# Sheet2.net
KiCad netlist of a schematic drawn in Altium Designer
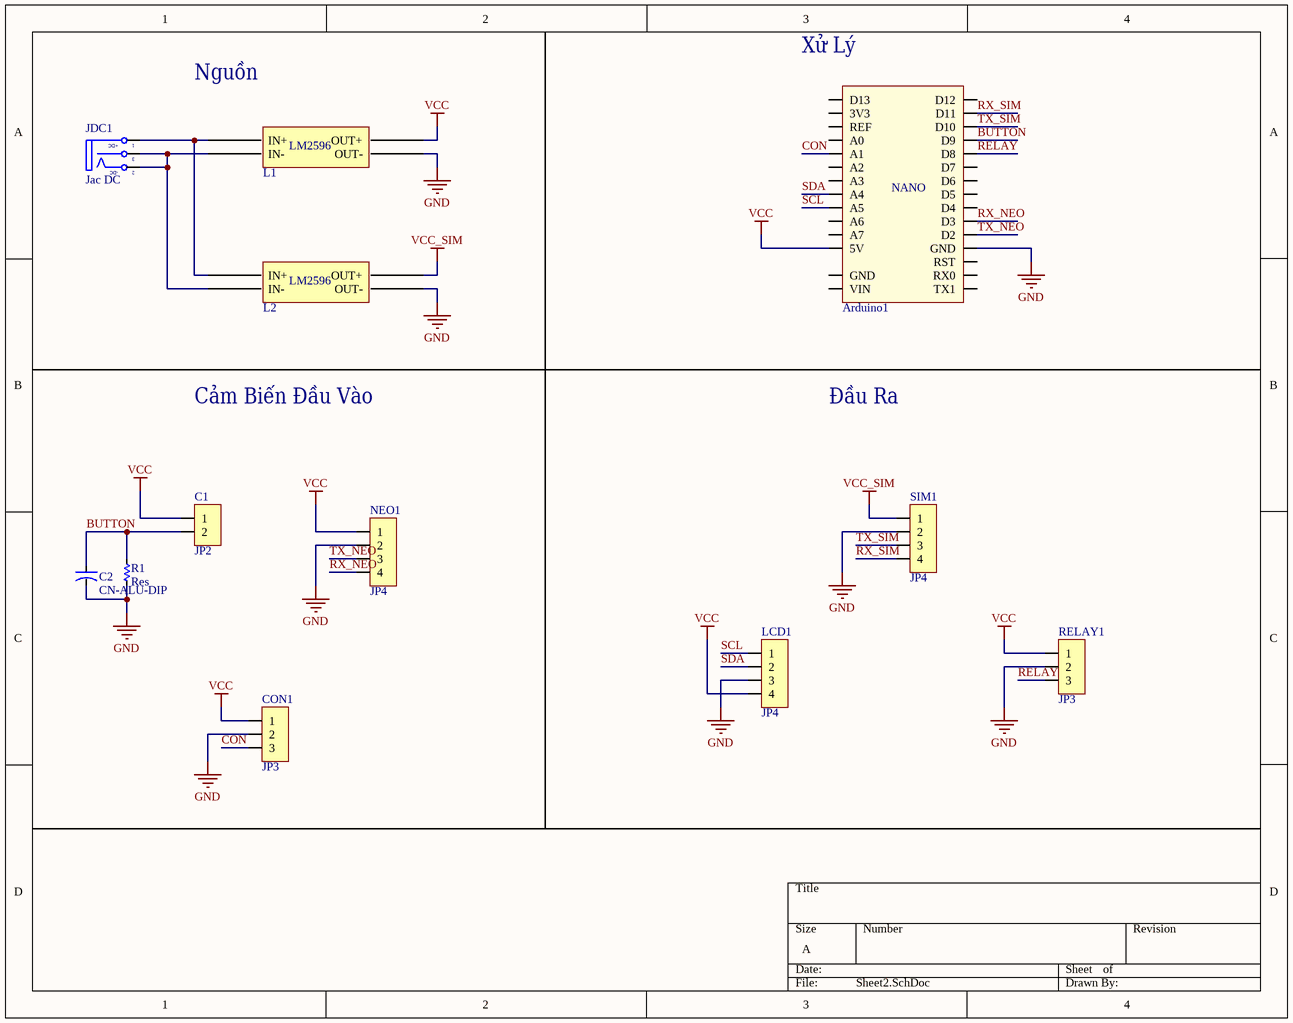
[diagram p0: Sheet2.SchDoc]

(export (version "E")
  (design (tool "Eeschema 10.0.6"))
  (components
    (comp (ref "Arduino1")
      (value "Arduino Nano")
      (footprint "Arduino Nano")
      (description "Arduino NANO")
      (libsource (lib "LIBRARY") (part "Arduino Nano"))
    )
    (comp (ref "C1")
      (value "JP2")
      (footprint "JP2-C1T")
      (description "WR-PHD 2.54 mm Angled Socket Header")
      (fields
        (field (name "MANUFACTURER") "Würth Elektronik eiSos GmbH")
        (field (name "PARTNO") "613002143121")
        (field (name "CREATED BY") "Karrer Zheng")
      )
      (libsource (lib "LIBRARY") (part "JP2"))
    )
    (comp (ref "C2")
      (value "CN-ALU-DIP")
      (footprint "CA-ALU-2.54")
      (description "Capacitor (Semiconductor SIM Model)")
      (fields (field (name "PUBLISHER") "Altium Limited"))
      (libsource (lib "LIBRARY") (part "CN-ALU-DIP"))
    )
    (comp (ref "CON1")
      (value "JP3")
      (footprint "JP3-C1T")
      (description "WR-PHD 2.54 mm Angled Socket Header")
      (fields
        (field (name "MANUFACTURER") "Würth Elektronik eiSos GmbH")
        (field (name "PARTNO") "613003143121")
        (field (name "CREATED BY") "Karrer Zheng")
      )
      (libsource (lib "LIBRARY") (part "JP3"))
    )
    (comp (ref "JDC1")
      (value "Jac DC")
      (footprint "DC0")
      (description "Jac DC input")
      (libsource (lib "LIBRARY") (part "DCIN"))
    )
    (comp (ref "L1")
      (value "BUCK_LM2596")
      (footprint "BUCK_LM2596")
      (libsource (lib "BUCK_LM2596_Sch") (part "BUCK_LM2596"))
    )
    (comp (ref "L2")
      (value "BUCK_LM2596")
      (footprint "BUCK_LM2596")
      (libsource (lib "BUCK_LM2596_Sch") (part "BUCK_LM2596"))
    )
    (comp (ref "LCD1")
      (value "JP4")
      (footprint "JP4-C1T")
      (description "WR-PHD 2.54 mm Angled Socket Header")
      (fields
        (field (name "MANUFACTURER") "Würth Elektronik eiSos GmbH")
        (field (name "PARTNO") "613004143121")
        (field (name "CREATED BY") "Karrer Zheng")
      )
      (libsource (lib "LIBRARY") (part "JP4"))
    )
    (comp (ref "NEO1")
      (value "JP4")
      (footprint "JP4-C1T")
      (description "WR-PHD 2.54 mm Angled Socket Header")
      (fields
        (field (name "MANUFACTURER") "Würth Elektronik eiSos GmbH")
        (field (name "PARTNO") "613004143121")
        (field (name "CREATED BY") "Karrer Zheng")
      )
      (libsource (lib "LIBRARY") (part "JP4"))
    )
    (comp (ref "R1")
      (value "Res")
      (footprint "RES-1/4W")
      (fields
        (field (name "MANUFACTURER") "Generic Components")
        (field (name "PUBLISHER") "Altium Hobart Technology Centre")
      )
      (libsource (lib "LIBRARY") (part "Res"))
    )
    (comp (ref "RELAY1")
      (value "JP3")
      (footprint "JP3-C1T")
      (description "WR-PHD 2.54 mm Angled Socket Header")
      (fields
        (field (name "MANUFACTURER") "Würth Elektronik eiSos GmbH")
        (field (name "PARTNO") "613003143121")
        (field (name "CREATED BY") "Karrer Zheng")
      )
      (libsource (lib "LIBRARY") (part "JP3"))
    )
    (comp (ref "SIM1")
      (value "JP4")
      (footprint "JP4-C1T")
      (description "WR-PHD 2.54 mm Angled Socket Header")
      (fields
        (field (name "MANUFACTURER") "Würth Elektronik eiSos GmbH")
        (field (name "PARTNO") "613004143121")
        (field (name "CREATED BY") "Karrer Zheng")
      )
      (libsource (lib "LIBRARY") (part "JP4"))
    )
  )
  (nets
    (net (code "1") (name "/BUTTON") (class "Default")
      (node (ref "Arduino1") (pin "D9") (pinfunction "D9_D9") (pintype "passive"))
      (node (ref "C1") (pin "2") (pinfunction "2_2") (pintype "passive"))
      (node (ref "C2") (pin "1") (pinfunction "1_1") (pintype "passive"))
      (node (ref "R1") (pin "1") (pinfunction "1_1") (pintype "passive"))
    )
    (net (code "2") (name "/CON") (class "Default")
      (node (ref "Arduino1") (pin "A1") (pinfunction "A1_A1") (pintype "passive"))
      (node (ref "CON1") (pin "3") (pinfunction "3_3") (pintype "passive"))
    )
    (net (code "3") (name "/RELAY") (class "Default")
      (node (ref "Arduino1") (pin "D8") (pinfunction "D8_D8") (pintype "passive"))
      (node (ref "RELAY1") (pin "3") (pinfunction "3_3") (pintype "passive"))
    )
    (net (code "4") (name "/RX_NEO") (class "Default")
      (node (ref "Arduino1") (pin "D3") (pinfunction "D3_D3") (pintype "passive"))
      (node (ref "NEO1") (pin "4") (pinfunction "4_4") (pintype "passive"))
    )
    (net (code "5") (name "/RX_SIM") (class "Default")
      (node (ref "Arduino1") (pin "D11") (pinfunction "D11_D11") (pintype "passive"))
      (node (ref "SIM1") (pin "4") (pinfunction "4_4") (pintype "passive"))
    )
    (net (code "6") (name "/SCL") (class "Default")
      (node (ref "Arduino1") (pin "A5") (pinfunction "A5_A5") (pintype "passive"))
      (node (ref "LCD1") (pin "1") (pinfunction "1_1") (pintype "passive"))
    )
    (net (code "7") (name "/SDA") (class "Default")
      (node (ref "Arduino1") (pin "A4") (pinfunction "A4_A4") (pintype "passive"))
      (node (ref "LCD1") (pin "2") (pinfunction "2_2") (pintype "passive"))
    )
    (net (code "8") (name "/TX_NEO") (class "Default")
      (node (ref "Arduino1") (pin "D2") (pinfunction "D2_D2") (pintype "passive"))
      (node (ref "NEO1") (pin "3") (pinfunction "3_3") (pintype "passive"))
    )
    (net (code "9") (name "/TX_SIM") (class "Default")
      (node (ref "Arduino1") (pin "D10") (pinfunction "D10_D10") (pintype "passive"))
      (node (ref "SIM1") (pin "3") (pinfunction "3_3") (pintype "passive"))
    )
    (net (code "10") (name "GND") (class "Default")
      (node (ref "Arduino1") (pin "GND") (pinfunction "GND_GND") (pintype "passive"))
      (node (ref "C2") (pin "2") (pinfunction "2_2") (pintype "passive"))
      (node (ref "CON1") (pin "2") (pinfunction "2_2") (pintype "passive"))
      (node (ref "L1") (pin "3") (pinfunction "OUT-_3") (pintype "passive"))
      (node (ref "L2") (pin "3") (pinfunction "OUT-_3") (pintype "passive"))
      (node (ref "LCD1") (pin "3") (pinfunction "3_3") (pintype "passive"))
      (node (ref "NEO1") (pin "2") (pinfunction "2_2") (pintype "passive"))
      (node (ref "R1") (pin "2") (pinfunction "2_2") (pintype "passive"))
      (node (ref "RELAY1") (pin "2") (pinfunction "2_2") (pintype "passive"))
      (node (ref "SIM1") (pin "2") (pinfunction "2_2") (pintype "passive"))
    )
    (net (code "11") (name "Net-(JDC1-S)") (class "Default")
      (node (ref "JDC1") (pin "2") (pinfunction "TN_2") (pintype "passive"))
      (node (ref "JDC1") (pin "3") (pinfunction "S_3") (pintype "power_in"))
      (node (ref "L1") (pin "2") (pinfunction "IN-_2") (pintype "passive"))
      (node (ref "L2") (pin "2") (pinfunction "IN-_2") (pintype "passive"))
    )
    (net (code "12") (name "Net-(JDC1-T)") (class "Default")
      (node (ref "JDC1") (pin "1") (pinfunction "T_1") (pintype "passive"))
      (node (ref "L1") (pin "1") (pinfunction "IN+_1") (pintype "passive"))
      (node (ref "L2") (pin "1") (pinfunction "IN+_1") (pintype "passive"))
    )
    (net (code "13") (name "VCC") (class "Default")
      (node (ref "Arduino1") (pin "5V") (pinfunction "5V_5V") (pintype "passive"))
      (node (ref "C1") (pin "1") (pinfunction "1_1") (pintype "passive"))
      (node (ref "CON1") (pin "1") (pinfunction "1_1") (pintype "passive"))
      (node (ref "L1") (pin "4") (pinfunction "OUT+_4") (pintype "passive"))
      (node (ref "LCD1") (pin "4") (pinfunction "4_4") (pintype "passive"))
      (node (ref "NEO1") (pin "1") (pinfunction "1_1") (pintype "passive"))
      (node (ref "RELAY1") (pin "1") (pinfunction "1_1") (pintype "passive"))
    )
    (net (code "14") (name "VCC_SIM") (class "Default")
      (node (ref "L2") (pin "4") (pinfunction "OUT+_4") (pintype "passive"))
      (node (ref "SIM1") (pin "1") (pinfunction "1_1") (pintype "passive"))
    )
    (net (code "15") (name "unconnected-(Arduino1-Pad3V3)") (class "Default")
      (node (ref "Arduino1") (pin "3V3") (pinfunction "3V3_3V3") (pintype "passive"))
    )
    (net (code "16") (name "unconnected-(Arduino1-PadA0)") (class "Default")
      (node (ref "Arduino1") (pin "A0") (pinfunction "A0_A0") (pintype "passive"))
    )
    (net (code "17") (name "unconnected-(Arduino1-PadA2)") (class "Default")
      (node (ref "Arduino1") (pin "A2") (pinfunction "A2_A2") (pintype "passive"))
    )
    (net (code "18") (name "unconnected-(Arduino1-PadA3)") (class "Default")
      (node (ref "Arduino1") (pin "A3") (pinfunction "A3_A3") (pintype "passive"))
    )
    (net (code "19") (name "unconnected-(Arduino1-PadA6)") (class "Default")
      (node (ref "Arduino1") (pin "A6") (pinfunction "A6_A6") (pintype "passive"))
    )
    (net (code "20") (name "unconnected-(Arduino1-PadA7)") (class "Default")
      (node (ref "Arduino1") (pin "A7") (pinfunction "A7_A7") (pintype "passive"))
    )
    (net (code "21") (name "unconnected-(Arduino1-PadD4)") (class "Default")
      (node (ref "Arduino1") (pin "D4") (pinfunction "D4_D4") (pintype "passive"))
    )
    (net (code "22") (name "unconnected-(Arduino1-PadD5)") (class "Default")
      (node (ref "Arduino1") (pin "D5") (pinfunction "D5_D5") (pintype "passive"))
    )
    (net (code "23") (name "unconnected-(Arduino1-PadD6)") (class "Default")
      (node (ref "Arduino1") (pin "D6") (pinfunction "D6_D6") (pintype "passive"))
    )
    (net (code "24") (name "unconnected-(Arduino1-PadD7)") (class "Default")
      (node (ref "Arduino1") (pin "D7") (pinfunction "D7_D7") (pintype "passive"))
    )
    (net (code "25") (name "unconnected-(Arduino1-PadD12)") (class "Default")
      (node (ref "Arduino1") (pin "D12") (pinfunction "D12_D12") (pintype "passive"))
    )
    (net (code "26") (name "unconnected-(Arduino1-PadD13)") (class "Default")
      (node (ref "Arduino1") (pin "D13") (pinfunction "D13_D13") (pintype "passive"))
    )
    (net (code "27") (name "unconnected-(Arduino1-PadGND)") (class "Default")
      (node (ref "Arduino1") (pin "GND") (pinfunction "GND_GND") (pintype "passive"))
    )
    (net (code "28") (name "unconnected-(Arduino1-PadREF)") (class "Default")
      (node (ref "Arduino1") (pin "REF") (pinfunction "REF_REF") (pintype "passive"))
    )
    (net (code "29") (name "unconnected-(Arduino1-PadRST)") (class "Default")
      (node (ref "Arduino1") (pin "RST") (pinfunction "RST_RST") (pintype "passive"))
    )
    (net (code "30") (name "unconnected-(Arduino1-PadRST)_1") (class "Default")
      (node (ref "Arduino1") (pin "RST") (pinfunction "RST_RST") (pintype "passive"))
    )
    (net (code "31") (name "unconnected-(Arduino1-PadRX0)") (class "Default")
      (node (ref "Arduino1") (pin "RX0") (pinfunction "RX0_RX0") (pintype "passive"))
    )
    (net (code "32") (name "unconnected-(Arduino1-PadTX1)") (class "Default")
      (node (ref "Arduino1") (pin "TX1") (pinfunction "TX1_TX1") (pintype "passive"))
    )
    (net (code "33") (name "unconnected-(Arduino1-PadVIN)") (class "Default")
      (node (ref "Arduino1") (pin "VIN") (pinfunction "VIN_VIN") (pintype "passive"))
    )
  )
)
